# stm32_board.net
KiCad netlist of a schematic drawn in EAGLE
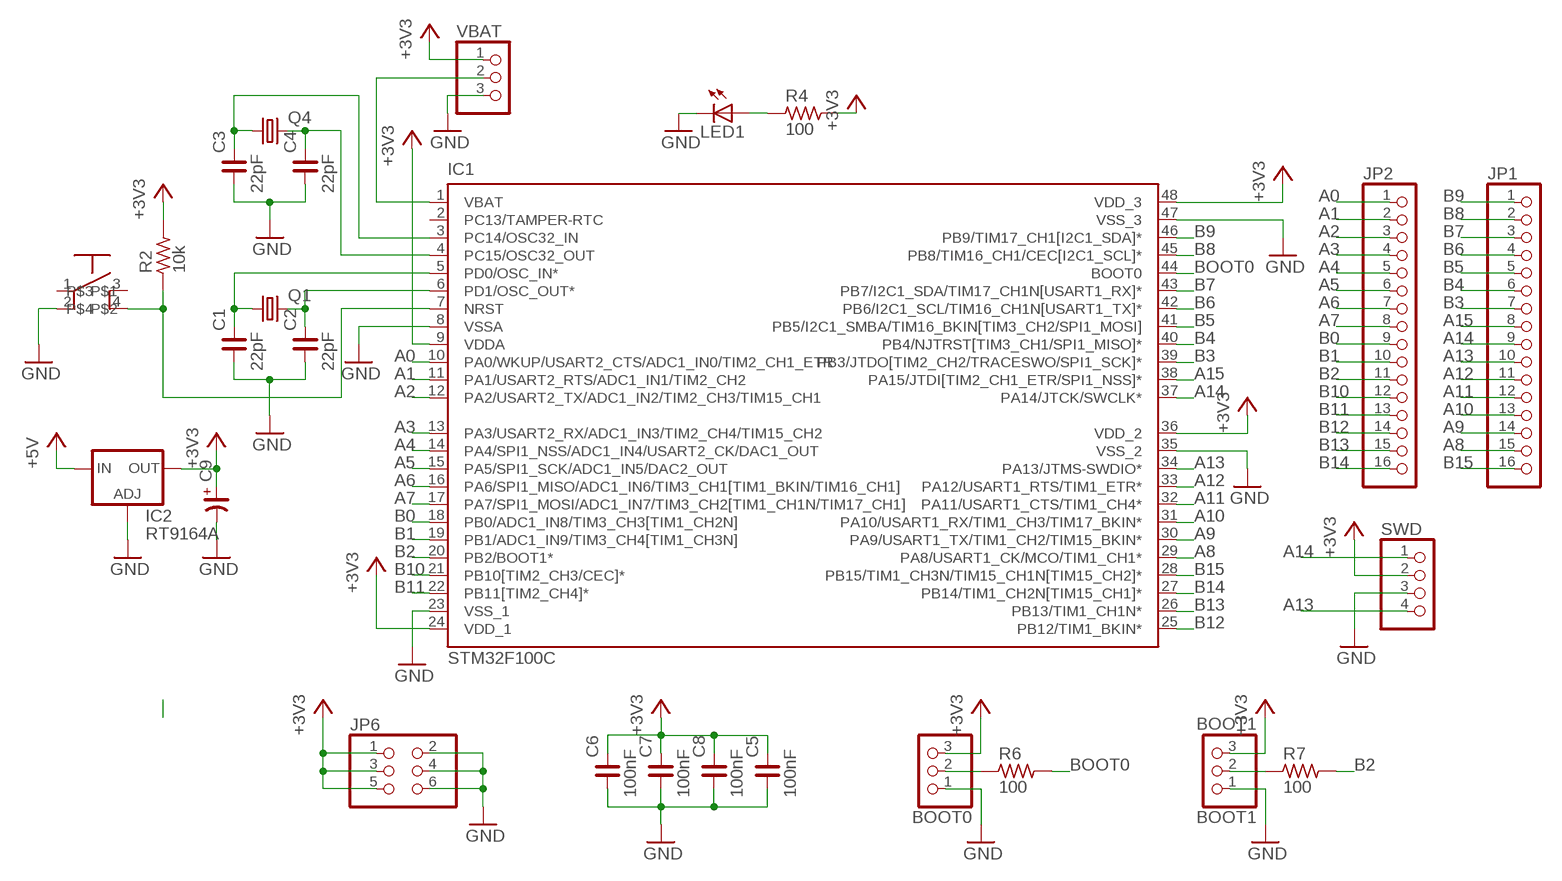
[diagram p0: schematic, sheet 1]

(export (version "E")
  (design (tool "Eeschema 10.0.6"))
  (components
    (comp (ref "BOOT0")
      (value "PINHD-1X3")
      (footprint "eagle-import:1X03")
      (libsource (lib "eagle-import") (part "PINHD-1X3"))
    )
    (comp (ref "BOOT1")
      (value "BOOT1")
      (footprint "eagle-import:1X03")
      (libsource (lib "eagle-import") (part "PINHD-1X3"))
    )
    (comp (ref "C1")
      (value "22pF")
      (footprint "eagle-import:C1206")
      (libsource (lib "eagle-import") (part "C_1206"))
    )
    (comp (ref "C2")
      (value "22pF")
      (footprint "eagle-import:C1206")
      (libsource (lib "eagle-import") (part "C_1206"))
    )
    (comp (ref "C3")
      (value "22pF")
      (footprint "eagle-import:C1206")
      (libsource (lib "eagle-import") (part "C_1206"))
    )
    (comp (ref "C4")
      (value "22pF")
      (footprint "eagle-import:C1206")
      (libsource (lib "eagle-import") (part "C_1206"))
    )
    (comp (ref "C5")
      (value "100nF")
      (footprint "eagle-import:C1206")
      (libsource (lib "eagle-import") (part "C_1206"))
    )
    (comp (ref "C6")
      (value "100nF")
      (footprint "eagle-import:C1206")
      (libsource (lib "eagle-import") (part "C_1206"))
    )
    (comp (ref "C7")
      (value "100nF")
      (footprint "eagle-import:C1206")
      (libsource (lib "eagle-import") (part "C_1206"))
    )
    (comp (ref "C8")
      (value "100nF")
      (footprint "eagle-import:C1206")
      (libsource (lib "eagle-import") (part "C_1206"))
    )
    (comp (ref "C9")
      (value "CP_SV-D")
      (footprint "eagle-import:CSV-D")
      (libsource (lib "eagle-import") (part "CP_SV-D"))
    )
    (comp (ref "IC1")
      (value "STM32F100C")
      (footprint "eagle-import:LQFP48")
      (libsource (lib "eagle-import") (part "STM32F100C"))
    )
    (comp (ref "IC2")
      (value "RT9164A")
      (footprint "eagle-import:DPACK")
      (libsource (lib "eagle-import") (part "LD117A?DT33TR"))
    )
    (comp (ref "JP1")
      (value "PINHD-1X16")
      (footprint "eagle-import:1X16")
      (libsource (lib "eagle-import") (part "PINHD-1X16"))
    )
    (comp (ref "JP2")
      (value "PINHD-1X16")
      (footprint "eagle-import:1X16")
      (libsource (lib "eagle-import") (part "PINHD-1X16"))
    )
    (comp (ref "JP6")
      (value "PINHD-2X3")
      (footprint "eagle-import:2X03")
      (libsource (lib "eagle-import") (part "PINHD-2X3"))
    )
    (comp (ref "LED1")
      (value "LEDCHIPLED_0805")
      (footprint "eagle-import:CHIPLED_0805")
      (libsource (lib "eagle-import") (part "LEDCHIPLED_0805"))
    )
    (comp (ref "Q1")
      (value "CRYSTALHC49U-V")
      (footprint "eagle-import:HC49U-V")
      (libsource (lib "eagle-import") (part "CRYSTALHC49U-V"))
    )
    (comp (ref "Q4")
      (value "CRYSTALTC26V")
      (footprint "eagle-import:TC26V")
      (libsource (lib "eagle-import") (part "CRYSTALTC26V"))
    )
    (comp (ref "R2")
      (value "10k")
      (footprint "eagle-import:R1206")
      (libsource (lib "eagle-import") (part "R_1206"))
    )
    (comp (ref "R4")
      (value "100")
      (footprint "eagle-import:R1206")
      (libsource (lib "eagle-import") (part "R_1206"))
    )
    (comp (ref "R6")
      (value "100")
      (footprint "eagle-import:R1206")
      (libsource (lib "eagle-import") (part "R_1206"))
    )
    (comp (ref "R7")
      (value "100")
      (footprint "eagle-import:R1206")
      (libsource (lib "eagle-import") (part "R_1206"))
    )
    (comp (ref "S1")
      (value "BUTTON")
      (footprint "eagle-import:BUTTON")
      (libsource (lib "eagle-import") (part "BUTTON"))
    )
    (comp (ref "SWD")
      (value "PINHD-1X4")
      (footprint "eagle-import:1X04")
      (libsource (lib "eagle-import") (part "PINHD-1X4"))
    )
    (comp (ref "VBAT")
      (value "PINHD-1X3")
      (footprint "eagle-import:1X03")
      (libsource (lib "eagle-import") (part "PINHD-1X3"))
    )
  )
  (nets
    (net (code "1") (name "+3V3") (class "Default")
      (node (ref "BOOT0") (pin "3") (pinfunction "3_3") (pintype "passive"))
      (node (ref "BOOT1") (pin "3") (pinfunction "3_3") (pintype "passive"))
      (node (ref "C5") (pin "2") (pinfunction "2_2") (pintype "passive"))
      (node (ref "C6") (pin "2") (pinfunction "2_2") (pintype "passive"))
      (node (ref "C7") (pin "2") (pinfunction "2_2") (pintype "passive"))
      (node (ref "C8") (pin "2") (pinfunction "2_2") (pintype "passive"))
      (node (ref "C9") (pin "+") (pinfunction "+_+") (pintype "passive"))
      (node (ref "IC1") (pin "24") (pinfunction "VDD_1_24") (pintype "power_in"))
      (node (ref "IC1") (pin "36") (pinfunction "VDD_2_36") (pintype "power_in"))
      (node (ref "IC1") (pin "48") (pinfunction "VDD_3_48") (pintype "power_in"))
      (node (ref "IC1") (pin "9") (pinfunction "VDDA_9") (pintype "power_in"))
      (node (ref "IC2") (pin "4") (pinfunction "OUT_4") (pintype "passive"))
      (node (ref "JP6") (pin "1") (pinfunction "1_1") (pintype "passive"))
      (node (ref "JP6") (pin "3") (pinfunction "3_3") (pintype "passive"))
      (node (ref "JP6") (pin "5") (pinfunction "5_5") (pintype "passive"))
      (node (ref "R2") (pin "2") (pinfunction "2_2") (pintype "passive"))
      (node (ref "R4") (pin "2") (pinfunction "2_2") (pintype "passive"))
      (node (ref "SWD") (pin "2") (pinfunction "2_2") (pintype "passive"))
      (node (ref "VBAT") (pin "1") (pinfunction "1_1") (pintype "passive"))
    )
    (net (code "2") (name "+5V") (class "Default")
      (node (ref "IC2") (pin "3") (pinfunction "IN_3") (pintype "input"))
    )
    (net (code "3") (name "/A0") (class "Default")
      (node (ref "IC1") (pin "10") (pinfunction "PA0/WKUP/USART2_CTS/ADC1_IN0/TIM2_CH1_ETR_10") (pintype "bidirectional"))
      (node (ref "JP2") (pin "1") (pinfunction "1_1") (pintype "passive"))
    )
    (net (code "4") (name "/A1") (class "Default")
      (node (ref "IC1") (pin "11") (pinfunction "PA1/USART2_RTS/ADC1_IN1/TIM2_CH2_11") (pintype "bidirectional"))
      (node (ref "JP2") (pin "2") (pinfunction "2_2") (pintype "passive"))
    )
    (net (code "5") (name "/A2") (class "Default")
      (node (ref "IC1") (pin "12") (pinfunction "PA2/USART2_TX/ADC1_IN2/TIM2_CH3/TIM15_CH1_12") (pintype "bidirectional"))
      (node (ref "JP2") (pin "3") (pinfunction "3_3") (pintype "passive"))
    )
    (net (code "6") (name "/A3") (class "Default")
      (node (ref "IC1") (pin "13") (pinfunction "PA3/USART2_RX/ADC1_IN3/TIM2_CH4/TIM15_CH2_13") (pintype "bidirectional"))
      (node (ref "JP2") (pin "4") (pinfunction "4_4") (pintype "passive"))
    )
    (net (code "7") (name "/A4") (class "Default")
      (node (ref "IC1") (pin "14") (pinfunction "PA4/SPI1_NSS/ADC1_IN4/USART2_CK/DAC1_OUT_14") (pintype "bidirectional"))
      (node (ref "JP2") (pin "5") (pinfunction "5_5") (pintype "passive"))
    )
    (net (code "8") (name "/A5") (class "Default")
      (node (ref "IC1") (pin "15") (pinfunction "PA5/SPI1_SCK/ADC1_IN5/DAC2_OUT_15") (pintype "bidirectional"))
      (node (ref "JP2") (pin "6") (pinfunction "6_6") (pintype "passive"))
    )
    (net (code "9") (name "/A6") (class "Default")
      (node (ref "IC1") (pin "16") (pinfunction "PA6/SPI1_MISO/ADC1_IN6/TIM3_CH1[TIM1_BKIN/TIM16_CH1]_16") (pintype "bidirectional"))
      (node (ref "JP2") (pin "7") (pinfunction "7_7") (pintype "passive"))
    )
    (net (code "10") (name "/A7") (class "Default")
      (node (ref "IC1") (pin "17") (pinfunction "PA7/SPI1_MOSI/ADC1_IN7/TIM3_CH2[TIM1_CH1N/TIM17_CH1]_17") (pintype "bidirectional"))
      (node (ref "JP2") (pin "8") (pinfunction "8_8") (pintype "passive"))
    )
    (net (code "11") (name "/A8") (class "Default")
      (node (ref "IC1") (pin "29") (pinfunction "PA8/USART1_CK/MCO/TIM1_CH1*_29") (pintype "bidirectional"))
      (node (ref "JP1") (pin "15") (pinfunction "15_15") (pintype "passive"))
    )
    (net (code "12") (name "/A9") (class "Default")
      (node (ref "IC1") (pin "30") (pinfunction "PA9/USART1_TX/TIM1_CH2/TIM15_BKIN*_30") (pintype "bidirectional"))
      (node (ref "JP1") (pin "14") (pinfunction "14_14") (pintype "passive"))
    )
    (net (code "13") (name "/A10") (class "Default")
      (node (ref "IC1") (pin "31") (pinfunction "PA10/USART1_RX/TIM1_CH3/TIM17_BKIN*_31") (pintype "bidirectional"))
      (node (ref "JP1") (pin "13") (pinfunction "13_13") (pintype "passive"))
    )
    (net (code "14") (name "/A11") (class "Default")
      (node (ref "IC1") (pin "32") (pinfunction "PA11/USART1_CTS/TIM1_CH4*_32") (pintype "bidirectional"))
      (node (ref "JP1") (pin "12") (pinfunction "12_12") (pintype "passive"))
    )
    (net (code "15") (name "/A12") (class "Default")
      (node (ref "IC1") (pin "33") (pinfunction "PA12/USART1_RTS/TIM1_ETR*_33") (pintype "bidirectional"))
      (node (ref "JP1") (pin "11") (pinfunction "11_11") (pintype "passive"))
    )
    (net (code "16") (name "/A13") (class "Default")
      (node (ref "IC1") (pin "34") (pinfunction "PA13/JTMS-SWDIO*_34") (pintype "bidirectional"))
      (node (ref "JP1") (pin "10") (pinfunction "10_10") (pintype "passive"))
      (node (ref "SWD") (pin "4") (pinfunction "4_4") (pintype "passive"))
    )
    (net (code "17") (name "/A14") (class "Default")
      (node (ref "IC1") (pin "37") (pinfunction "PA14/JTCK/SWCLK*_37") (pintype "bidirectional"))
      (node (ref "JP1") (pin "9") (pinfunction "9_9") (pintype "passive"))
      (node (ref "SWD") (pin "1") (pinfunction "1_1") (pintype "passive"))
    )
    (net (code "18") (name "/A15") (class "Default")
      (node (ref "IC1") (pin "38") (pinfunction "PA15/JTDI[TIM2_CH1_ETR/SPI1_NSS]*_38") (pintype "bidirectional"))
      (node (ref "JP1") (pin "8") (pinfunction "8_8") (pintype "passive"))
    )
    (net (code "19") (name "/B0") (class "Default")
      (node (ref "IC1") (pin "18") (pinfunction "PB0/ADC1_IN8/TIM3_CH3[TIM1_CH2N]_18") (pintype "bidirectional"))
      (node (ref "JP2") (pin "9") (pinfunction "9_9") (pintype "passive"))
    )
    (net (code "20") (name "/B1") (class "Default")
      (node (ref "IC1") (pin "19") (pinfunction "PB1/ADC1_IN9/TIM3_CH4[TIM1_CH3N]_19") (pintype "bidirectional"))
      (node (ref "JP2") (pin "10") (pinfunction "10_10") (pintype "passive"))
    )
    (net (code "21") (name "/B2") (class "Default")
      (node (ref "IC1") (pin "20") (pinfunction "PB2/BOOT1*_20") (pintype "bidirectional"))
      (node (ref "JP2") (pin "11") (pinfunction "11_11") (pintype "passive"))
      (node (ref "R7") (pin "2") (pinfunction "2_2") (pintype "passive"))
    )
    (net (code "22") (name "/B3") (class "Default")
      (node (ref "IC1") (pin "39") (pinfunction "PB3/JTDO[TIM2_CH2/TRACESWO/SPI1_SCK]*_39") (pintype "bidirectional"))
      (node (ref "JP1") (pin "7") (pinfunction "7_7") (pintype "passive"))
    )
    (net (code "23") (name "/B4") (class "Default")
      (node (ref "IC1") (pin "40") (pinfunction "PB4/NJTRST[TIM3_CH1/SPI1_MISO]*_40") (pintype "bidirectional"))
      (node (ref "JP1") (pin "6") (pinfunction "6_6") (pintype "passive"))
    )
    (net (code "24") (name "/B5") (class "Default")
      (node (ref "IC1") (pin "41") (pinfunction "PB5/I2C1_SMBA/TIM16_BKIN[TIM3_CH2/SPI1_MOSI]_41") (pintype "bidirectional"))
      (node (ref "JP1") (pin "5") (pinfunction "5_5") (pintype "passive"))
    )
    (net (code "25") (name "/B6") (class "Default")
      (node (ref "IC1") (pin "42") (pinfunction "PB6/I2C1_SCL/TIM16_CH1N[USART1_TX]*_42") (pintype "bidirectional"))
      (node (ref "JP1") (pin "4") (pinfunction "4_4") (pintype "passive"))
    )
    (net (code "26") (name "/B7") (class "Default")
      (node (ref "IC1") (pin "43") (pinfunction "PB7/I2C1_SDA/TIM17_CH1N[USART1_RX]*_43") (pintype "bidirectional"))
      (node (ref "JP1") (pin "3") (pinfunction "3_3") (pintype "passive"))
    )
    (net (code "27") (name "/B8") (class "Default")
      (node (ref "IC1") (pin "45") (pinfunction "PB8/TIM16_CH1/CEC[I2C1_SCL]*_45") (pintype "bidirectional"))
      (node (ref "JP1") (pin "2") (pinfunction "2_2") (pintype "passive"))
    )
    (net (code "28") (name "/B9") (class "Default")
      (node (ref "IC1") (pin "46") (pinfunction "PB9/TIM17_CH1[I2C1_SDA]*_46") (pintype "bidirectional"))
      (node (ref "JP1") (pin "1") (pinfunction "1_1") (pintype "passive"))
    )
    (net (code "29") (name "/B10") (class "Default")
      (node (ref "IC1") (pin "21") (pinfunction "PB10[TIM2_CH3/CEC]*_21") (pintype "bidirectional"))
      (node (ref "JP2") (pin "12") (pinfunction "12_12") (pintype "passive"))
    )
    (net (code "30") (name "/B11") (class "Default")
      (node (ref "IC1") (pin "22") (pinfunction "PB11[TIM2_CH4]*_22") (pintype "bidirectional"))
      (node (ref "JP2") (pin "13") (pinfunction "13_13") (pintype "passive"))
    )
    (net (code "31") (name "/B12") (class "Default")
      (node (ref "IC1") (pin "25") (pinfunction "PB12/TIM1_BKIN*_25") (pintype "bidirectional"))
      (node (ref "JP2") (pin "14") (pinfunction "14_14") (pintype "passive"))
    )
    (net (code "32") (name "/B13") (class "Default")
      (node (ref "IC1") (pin "26") (pinfunction "PB13/TIM1_CH1N*_26") (pintype "bidirectional"))
      (node (ref "JP2") (pin "15") (pinfunction "15_15") (pintype "passive"))
    )
    (net (code "33") (name "/B14") (class "Default")
      (node (ref "IC1") (pin "27") (pinfunction "PB14/TIM1_CH2N[TIM15_CH1]*_27") (pintype "bidirectional"))
      (node (ref "JP2") (pin "16") (pinfunction "16_16") (pintype "passive"))
    )
    (net (code "34") (name "/B15") (class "Default")
      (node (ref "IC1") (pin "28") (pinfunction "PB15/TIM1_CH3N/TIM15_CH1N[TIM15_CH2]*_28") (pintype "bidirectional"))
      (node (ref "JP1") (pin "16") (pinfunction "16_16") (pintype "passive"))
    )
    (net (code "35") (name "/BOOT0") (class "Default")
      (node (ref "IC1") (pin "44") (pinfunction "BOOT0_44") (pintype "input"))
      (node (ref "R6") (pin "2") (pinfunction "2_2") (pintype "passive"))
    )
    (net (code "36") (name "GND") (class "Default")
      (node (ref "BOOT0") (pin "1") (pinfunction "1_1") (pintype "passive"))
      (node (ref "BOOT1") (pin "1") (pinfunction "1_1") (pintype "passive"))
      (node (ref "C1") (pin "1") (pinfunction "1_1") (pintype "passive"))
      (node (ref "C2") (pin "1") (pinfunction "1_1") (pintype "passive"))
      (node (ref "C3") (pin "1") (pinfunction "1_1") (pintype "passive"))
      (node (ref "C4") (pin "1") (pinfunction "1_1") (pintype "passive"))
      (node (ref "C5") (pin "1") (pinfunction "1_1") (pintype "passive"))
      (node (ref "C6") (pin "1") (pinfunction "1_1") (pintype "passive"))
      (node (ref "C7") (pin "1") (pinfunction "1_1") (pintype "passive"))
      (node (ref "C8") (pin "1") (pinfunction "1_1") (pintype "passive"))
      (node (ref "C9") (pin "-") (pinfunction "-_-") (pintype "passive"))
      (node (ref "IC1") (pin "23") (pinfunction "VSS_1_23") (pintype "power_in"))
      (node (ref "IC1") (pin "35") (pinfunction "VSS_2_35") (pintype "power_in"))
      (node (ref "IC1") (pin "47") (pinfunction "VSS_3_47") (pintype "power_in"))
      (node (ref "IC1") (pin "8") (pinfunction "VSSA_8") (pintype "power_in"))
      (node (ref "IC2") (pin "1") (pinfunction "ADJ_1") (pintype "input"))
      (node (ref "JP6") (pin "2") (pinfunction "2_2") (pintype "passive"))
      (node (ref "JP6") (pin "4") (pinfunction "4_4") (pintype "passive"))
      (node (ref "JP6") (pin "6") (pinfunction "6_6") (pintype "passive"))
      (node (ref "LED1") (pin "C") (pinfunction "C_C") (pintype "passive"))
      (node (ref "S1") (pin "2") (pinfunction "P$2_2") (pintype "passive"))
      (node (ref "SWD") (pin "3") (pinfunction "3_3") (pintype "passive"))
      (node (ref "VBAT") (pin "3") (pinfunction "3_3") (pintype "passive"))
    )
    (net (code "37") (name "Net-(BOOT0-Pad2)") (class "Default")
      (node (ref "BOOT0") (pin "2") (pinfunction "2_2") (pintype "passive"))
      (node (ref "R6") (pin "1") (pinfunction "1_1") (pintype "passive"))
    )
    (net (code "38") (name "Net-(BOOT1-Pad2)") (class "Default")
      (node (ref "BOOT1") (pin "2") (pinfunction "2_2") (pintype "passive"))
      (node (ref "R7") (pin "1") (pinfunction "1_1") (pintype "passive"))
    )
    (net (code "39") (name "Net-(IC1-NRST)") (class "Default")
      (node (ref "IC1") (pin "7") (pinfunction "NRST_7") (pintype "bidirectional"))
      (node (ref "R2") (pin "1") (pinfunction "1_1") (pintype "passive"))
      (node (ref "S1") (pin "4") (pinfunction "P$4_4") (pintype "passive"))
    )
    (net (code "40") (name "Net-(IC1-PC14{slash}OSC32_IN)") (class "Default")
      (node (ref "C3") (pin "2") (pinfunction "2_2") (pintype "passive"))
      (node (ref "IC1") (pin "3") (pinfunction "PC14/OSC32_IN_3") (pintype "bidirectional"))
      (node (ref "Q4") (pin "1") (pinfunction "1_1") (pintype "passive"))
    )
    (net (code "41") (name "Net-(IC1-PC15{slash}OSC32_OUT)") (class "Default")
      (node (ref "C4") (pin "2") (pinfunction "2_2") (pintype "passive"))
      (node (ref "IC1") (pin "4") (pinfunction "PC15/OSC32_OUT_4") (pintype "bidirectional"))
      (node (ref "Q4") (pin "2") (pinfunction "2_2") (pintype "passive"))
    )
    (net (code "42") (name "Net-(IC1-PD0{slash}OSC_IN*)") (class "Default")
      (node (ref "C1") (pin "2") (pinfunction "2_2") (pintype "passive"))
      (node (ref "IC1") (pin "5") (pinfunction "PD0/OSC_IN*_5") (pintype "bidirectional"))
      (node (ref "Q1") (pin "1") (pinfunction "1_1") (pintype "passive"))
    )
    (net (code "43") (name "Net-(IC1-PD1{slash}OSC_OUT*)") (class "Default")
      (node (ref "C2") (pin "2") (pinfunction "2_2") (pintype "passive"))
      (node (ref "IC1") (pin "6") (pinfunction "PD1/OSC_OUT*_6") (pintype "bidirectional"))
      (node (ref "Q1") (pin "2") (pinfunction "2_2") (pintype "passive"))
    )
    (net (code "44") (name "Net-(IC1-VBAT)") (class "Default")
      (node (ref "IC1") (pin "1") (pinfunction "VBAT_1") (pintype "power_in"))
      (node (ref "VBAT") (pin "2") (pinfunction "2_2") (pintype "passive"))
    )
    (net (code "45") (name "Net-(LED1-PadA)") (class "Default")
      (node (ref "LED1") (pin "A") (pinfunction "A_A") (pintype "passive"))
      (node (ref "R4") (pin "1") (pinfunction "1_1") (pintype "passive"))
    )
    (net (code "46") (name "unconnected-(IC1-PC13{slash}TAMPER-RTC-Pad2)") (class "Default")
      (node (ref "IC1") (pin "2") (pinfunction "PC13/TAMPER-RTC_2") (pintype "bidirectional"))
    )
    (net (code "47") (name "unconnected-(S1-P$1-Pad1)") (class "Default")
      (node (ref "S1") (pin "1") (pinfunction "P$1_1") (pintype "passive"))
    )
    (net (code "48") (name "unconnected-(S1-P$3-Pad3)") (class "Default")
      (node (ref "S1") (pin "3") (pinfunction "P$3_3") (pintype "passive"))
    )
  )
)
